# OpAmp.net
KiCad netlist of a schematic drawn in Altium Designer
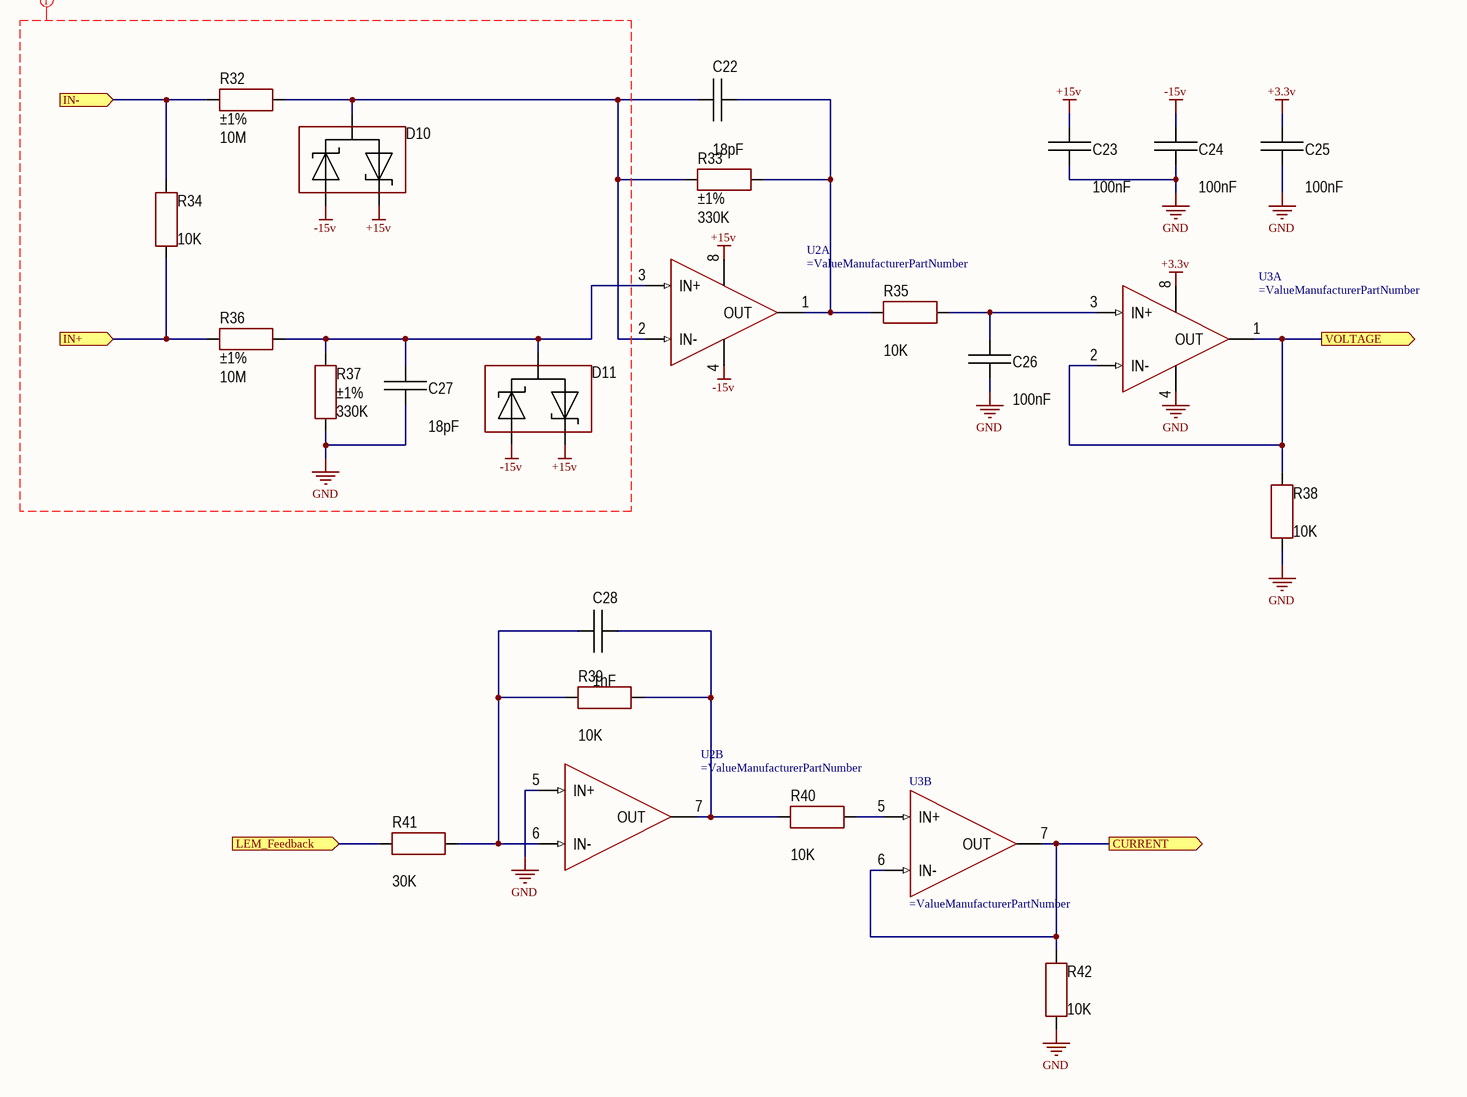
[diagram p0: OpAmp.SchDoc]

(export (version "E")
  (design (tool "Eeschema 10.0.6"))
  (components
    (comp (ref "C22")
      (value "18pF")
      (footprint "StandardCase:CAP: 1206")
      (fields
        (field (name "MANUFACTURER") "Yageo")
        (field (name "PARTNUMBER") "CC1206KRX7R9BB104")
        (field (name "VALUEMANUFACTURERPARTNUMBER") "Ceramic capacitor, 18pF, 1206")
      )
      (libsource (lib "Capacitor") (part "Ceramic_1206"))
    )
    (comp (ref "C23")
      (value "100nF")
      (footprint "StandardCase:CAP: 1206")
      (fields
        (field (name "MANUFACTURER") "Yageo")
        (field (name "PARTNUMBER") "CC1206KRX7R9BB104")
        (field (name "VALUEMANUFACTURERPARTNUMBER") "Ceramic capacitor, 100nF, 1206")
      )
      (libsource (lib "Capacitor") (part "Ceramic_1206"))
    )
    (comp (ref "C24")
      (value "100nF")
      (footprint "StandardCase:CAP: 1206")
      (fields
        (field (name "MANUFACTURER") "Yageo")
        (field (name "PARTNUMBER") "CC1206KRX7R9BB104")
        (field (name "VALUEMANUFACTURERPARTNUMBER") "Ceramic capacitor, 100nF, 1206")
      )
      (libsource (lib "Capacitor") (part "Ceramic_1206"))
    )
    (comp (ref "C25")
      (value "100nF")
      (footprint "StandardCase:CAP: 1206")
      (fields
        (field (name "MANUFACTURER") "Yageo")
        (field (name "PARTNUMBER") "CC1206KRX7R9BB104")
        (field (name "VALUEMANUFACTURERPARTNUMBER") "Ceramic capacitor, 100nF, 1206")
      )
      (libsource (lib "Capacitor") (part "Ceramic_1206"))
    )
    (comp (ref "C26")
      (value "100nF")
      (footprint "StandardCase:CAP: 1206")
      (fields
        (field (name "MANUFACTURER") "Yageo")
        (field (name "PARTNUMBER") "CC1206KRX7R9BB104")
        (field (name "VALUEMANUFACTURERPARTNUMBER") "Ceramic capacitor, 100nF, 1206")
      )
      (libsource (lib "Capacitor") (part "Ceramic_1206"))
    )
    (comp (ref "C27")
      (value "18pF")
      (footprint "StandardCase:CAP: 1206")
      (fields
        (field (name "MANUFACTURER") "Yageo")
        (field (name "PARTNUMBER") "CC1206KRX7R9BB104")
        (field (name "VALUEMANUFACTURERPARTNUMBER") "Ceramic capacitor, 18pF, 1206")
      )
      (libsource (lib "Capacitor") (part "Ceramic_1206"))
    )
    (comp (ref "C28")
      (value "1nF")
      (footprint "StandardCase:CAP: 1206")
      (fields
        (field (name "MANUFACTURER") "Yageo")
        (field (name "PARTNUMBER") "CC1206KRX7R9BB104")
        (field (name "VALUEMANUFACTURERPARTNUMBER") "Ceramic capacitor, 1nF, 1206")
      )
      (libsource (lib "Capacitor") (part "Ceramic_1206"))
    )
    (comp (ref "D10")
      (value "~")
      (footprint "StandardCase:SOT23")
      (fields
        (field (name "MANUFACTURER") "Diodes Incorporated")
        (field (name "VALUEMANUFACTURERPARTNUMBER") "BAS40-04, SOT23-3")
        (field (name "VOLTAGE") "40V")
      )
      (libsource (lib "Diode") (part "Schottky_array"))
    )
    (comp (ref "D11")
      (value "~")
      (footprint "StandardCase:SOT23")
      (fields
        (field (name "MANUFACTURER") "Diodes Incorporated")
        (field (name "VALUEMANUFACTURERPARTNUMBER") "BAS40-04, SOT23-3")
        (field (name "VOLTAGE") "40V")
      )
      (libsource (lib "Diode") (part "Schottky_array"))
    )
    (comp (ref "R32")
      (value "10M")
      (footprint "PcbLib1:CFR-50")
      (fields
        (field (name "MANUFACTURER") "Yageo")
        (field (name "PARTNUMBER") "RC1206JR-07100RL")
        (field (name "VALUEMANUFACTURERPARTNUMBER") "Resistor, 10M, CFR-50")
        (field (name "TOLERANCE") "±1%")
      )
      (libsource (lib "") (part "Resistor_1206_2"))
    )
    (comp (ref "R33")
      (value "330K")
      (footprint "StandardCase:RES: 1206")
      (fields
        (field (name "MANUFACTURER") "Yageo")
        (field (name "PARTNUMBER") "RC1206JR-07100RL")
        (field (name "VALUEMANUFACTURERPARTNUMBER") "Resistor, 330K, 1206")
        (field (name "TOLERANCE") "±1%")
      )
      (libsource (lib "") (part "Resistor_1206_1"))
    )
    (comp (ref "R34")
      (value "10K")
      (footprint "PcbLib1:CPF-3")
      (fields
        (field (name "MANUFACTURER") "Yageo")
        (field (name "PARTNUMBER") "RC1206JR-07100RL")
        (field (name "VALUEMANUFACTURERPARTNUMBER") "Resistor, 10K, CPF-3")
      )
      (libsource (lib "Resistor") (part "Resistor_1206"))
    )
    (comp (ref "R35")
      (value "10K")
      (footprint "StandardCase:RES: 1206")
      (fields
        (field (name "MANUFACTURER") "Yageo")
        (field (name "PARTNUMBER") "RC1206JR-07100RL")
        (field (name "VALUEMANUFACTURERPARTNUMBER") "Resistor, 10K, 1206")
      )
      (libsource (lib "") (part "Resistor_1206_1"))
    )
    (comp (ref "R36")
      (value "10M")
      (footprint "PcbLib1:CFR-50")
      (fields
        (field (name "MANUFACTURER") "Yageo")
        (field (name "PARTNUMBER") "RC1206JR-07100RL")
        (field (name "VALUEMANUFACTURERPARTNUMBER") "Resistor, 10M, CFR-50")
        (field (name "TOLERANCE") "±1%")
      )
      (libsource (lib "") (part "Resistor_1206_1"))
    )
    (comp (ref "R37")
      (value "330K")
      (footprint "StandardCase:RES: 1206")
      (fields
        (field (name "MANUFACTURER") "Yageo")
        (field (name "PARTNUMBER") "RC1206JR-07100RL")
        (field (name "VALUEMANUFACTURERPARTNUMBER") "Resistor, 330K, 1206")
        (field (name "TOLERANCE") "±1%")
      )
      (libsource (lib "Resistor") (part "Resistor_1206"))
    )
    (comp (ref "R38")
      (value "10K")
      (footprint "StandardCase:RES: 1206")
      (fields
        (field (name "MANUFACTURER") "Yageo")
        (field (name "PARTNUMBER") "RC1206JR-07100RL")
        (field (name "VALUEMANUFACTURERPARTNUMBER") "Resistor, 10K, 1206")
      )
      (libsource (lib "Resistor") (part "Resistor_1206"))
    )
    (comp (ref "R39")
      (value "10K")
      (footprint "StandardCase:RES: 1206")
      (fields
        (field (name "MANUFACTURER") "Yageo")
        (field (name "PARTNUMBER") "RC1206JR-07100RL")
        (field (name "VALUEMANUFACTURERPARTNUMBER") "Resistor, 10K, 1206")
      )
      (libsource (lib "") (part "Resistor_1206_1"))
    )
    (comp (ref "R40")
      (value "10K")
      (footprint "StandardCase:RES: 1206")
      (fields
        (field (name "MANUFACTURER") "Yageo")
        (field (name "PARTNUMBER") "RC1206JR-07100RL")
        (field (name "VALUEMANUFACTURERPARTNUMBER") "Resistor, 10K, 1206")
      )
      (libsource (lib "") (part "Resistor_1206_1"))
    )
    (comp (ref "R41")
      (value "30K")
      (footprint "StandardCase:RES: 1206")
      (fields
        (field (name "MANUFACTURER") "Yageo")
        (field (name "PARTNUMBER") "RC1206JR-07100RL")
        (field (name "VALUEMANUFACTURERPARTNUMBER") "Resistor, 30K, 1206")
      )
      (libsource (lib "") (part "Resistor_1206_1"))
    )
    (comp (ref "R42")
      (value "10K")
      (footprint "StandardCase:RES: 1206")
      (fields
        (field (name "MANUFACTURER") "Yageo")
        (field (name "PARTNUMBER") "RC1206JR-07100RL")
        (field (name "VALUEMANUFACTURERPARTNUMBER") "Resistor, 10K, 1206")
      )
      (libsource (lib "Resistor") (part "Resistor_1206"))
    )
    (comp (ref "U2")
      (value "~")
      (footprint "StandardCase:8-SOIC")
      (fields
        (field (name "PARTNUMBER") "LF253")
        (field (name "VALUEMANUFACTURERPARTNUMBER") "LF253, SOIC-8")
      )
      (libsource (lib "Schlib1") (part "LF253"))
    )
    (comp (ref "U3")
      (value "~")
      (footprint "StandardCase:8-SOIC")
      (fields
        (field (name "PARTNUMBER") "MC33202")
        (field (name "VALUEMANUFACTURERPARTNUMBER") "MC33202, SOIC-8")
      )
      (libsource (lib "Schlib1") (part "MC33202"))
    )
  )
  (nets
    (net (code "1") (name "+3.3v") (class "Default")
      (node (ref "C25") (pin "2") (pinfunction "2_2") (pintype "power_in"))
      (node (ref "U3") (pin "8") (pinfunction "V+_8") (pintype "power_in"))
    )
    (net (code "2") (name "+15v") (class "Default")
      (node (ref "C23") (pin "2") (pinfunction "2_2") (pintype "power_in"))
      (node (ref "D10") (pin "2") (pinfunction "2_2") (pintype "passive"))
      (node (ref "D11") (pin "2") (pinfunction "2_2") (pintype "passive"))
      (node (ref "U2") (pin "8") (pinfunction "V+_8") (pintype "power_in"))
    )
    (net (code "3") (name "-15v") (class "Default")
      (node (ref "C24") (pin "2") (pinfunction "2_2") (pintype "power_in"))
      (node (ref "D10") (pin "1") (pinfunction "1_1") (pintype "passive"))
      (node (ref "D11") (pin "1") (pinfunction "1_1") (pintype "passive"))
      (node (ref "U2") (pin "4") (pinfunction "V-_4") (pintype "power_in"))
    )
    (net (code "4") (name "/CURRENT") (class "Default")
      (node (ref "R42") (pin "2") (pinfunction "2_2") (pintype "passive"))
      (node (ref "U3") (pin "6") (pinfunction "IN-_6") (pintype "input"))
      (node (ref "U3") (pin "7") (pinfunction "OUT_7") (pintype "power_in"))
    )
    (net (code "5") (name "/IN+") (class "Default")
      (node (ref "R34") (pin "1") (pinfunction "1_1") (pintype "passive"))
      (node (ref "R36") (pin "1") (pinfunction "1_1") (pintype "passive"))
    )
    (net (code "6") (name "/IN-") (class "Default")
      (node (ref "R32") (pin "2") (pinfunction "2_2") (pintype "passive"))
      (node (ref "R34") (pin "2") (pinfunction "2_2") (pintype "passive"))
    )
    (net (code "7") (name "/LEM_Feedback") (class "Default")
      (node (ref "R41") (pin "1") (pinfunction "1_1") (pintype "passive"))
    )
    (net (code "8") (name "/VOLTAGE") (class "Default")
      (node (ref "R38") (pin "2") (pinfunction "2_2") (pintype "passive"))
      (node (ref "U3") (pin "1") (pinfunction "OUT_1") (pintype "power_in"))
      (node (ref "U3") (pin "2") (pinfunction "IN-_2") (pintype "input"))
    )
    (net (code "9") (name "GND") (class "Default")
      (node (ref "C23") (pin "1") (pinfunction "1_1") (pintype "power_in"))
      (node (ref "C24") (pin "1") (pinfunction "1_1") (pintype "power_in"))
      (node (ref "C25") (pin "1") (pinfunction "1_1") (pintype "power_in"))
      (node (ref "C26") (pin "1") (pinfunction "1_1") (pintype "power_in"))
      (node (ref "C27") (pin "1") (pinfunction "1_1") (pintype "power_in"))
      (node (ref "R37") (pin "1") (pinfunction "1_1") (pintype "passive"))
      (node (ref "R38") (pin "1") (pinfunction "1_1") (pintype "passive"))
      (node (ref "R42") (pin "1") (pinfunction "1_1") (pintype "passive"))
      (node (ref "U2") (pin "5") (pinfunction "IN+_5") (pintype "input"))
      (node (ref "U3") (pin "4") (pinfunction "V-_4") (pintype "power_in"))
    )
    (net (code "10") (name "Net-(U2A-IN+)") (class "Default")
      (node (ref "C27") (pin "2") (pinfunction "2_2") (pintype "power_in"))
      (node (ref "D11") (pin "3") (pinfunction "3_3") (pintype "passive"))
      (node (ref "R36") (pin "2") (pinfunction "2_2") (pintype "passive"))
      (node (ref "R37") (pin "2") (pinfunction "2_2") (pintype "passive"))
      (node (ref "U2") (pin "3") (pinfunction "IN+_3") (pintype "input"))
    )
    (net (code "11") (name "Net-(U2A-IN-)") (class "Default")
      (node (ref "C22") (pin "2") (pinfunction "2_2") (pintype "power_in"))
      (node (ref "D10") (pin "3") (pinfunction "3_3") (pintype "passive"))
      (node (ref "R32") (pin "1") (pinfunction "1_1") (pintype "passive"))
      (node (ref "R33") (pin "1") (pinfunction "1_1") (pintype "passive"))
      (node (ref "U2") (pin "2") (pinfunction "IN-_2") (pintype "input"))
    )
    (net (code "12") (name "Net-(U2A-OUT)") (class "Default")
      (node (ref "C22") (pin "1") (pinfunction "1_1") (pintype "power_in"))
      (node (ref "R33") (pin "2") (pinfunction "2_2") (pintype "passive"))
      (node (ref "R35") (pin "1") (pinfunction "1_1") (pintype "passive"))
      (node (ref "U2") (pin "1") (pinfunction "OUT_1") (pintype "power_in"))
    )
    (net (code "13") (name "Net-(U2B-IN-)") (class "Default")
      (node (ref "C28") (pin "2") (pinfunction "2_2") (pintype "power_in"))
      (node (ref "R39") (pin "1") (pinfunction "1_1") (pintype "passive"))
      (node (ref "R41") (pin "2") (pinfunction "2_2") (pintype "passive"))
      (node (ref "U2") (pin "6") (pinfunction "IN-_6") (pintype "input"))
    )
    (net (code "14") (name "Net-(U2B-OUT)") (class "Default")
      (node (ref "C28") (pin "1") (pinfunction "1_1") (pintype "power_in"))
      (node (ref "R39") (pin "2") (pinfunction "2_2") (pintype "passive"))
      (node (ref "R40") (pin "1") (pinfunction "1_1") (pintype "passive"))
      (node (ref "U2") (pin "7") (pinfunction "OUT_7") (pintype "power_in"))
    )
    (net (code "15") (name "Net-(U3A-IN+)") (class "Default")
      (node (ref "C26") (pin "2") (pinfunction "2_2") (pintype "power_in"))
      (node (ref "R35") (pin "2") (pinfunction "2_2") (pintype "passive"))
      (node (ref "U3") (pin "3") (pinfunction "IN+_3") (pintype "input"))
    )
    (net (code "16") (name "Net-(U3B-IN+)") (class "Default")
      (node (ref "R40") (pin "2") (pinfunction "2_2") (pintype "passive"))
      (node (ref "U3") (pin "5") (pinfunction "IN+_5") (pintype "input"))
    )
  )
)
